# 2_byte_input.net
KiCad netlist of a schematic drawn in EAGLE
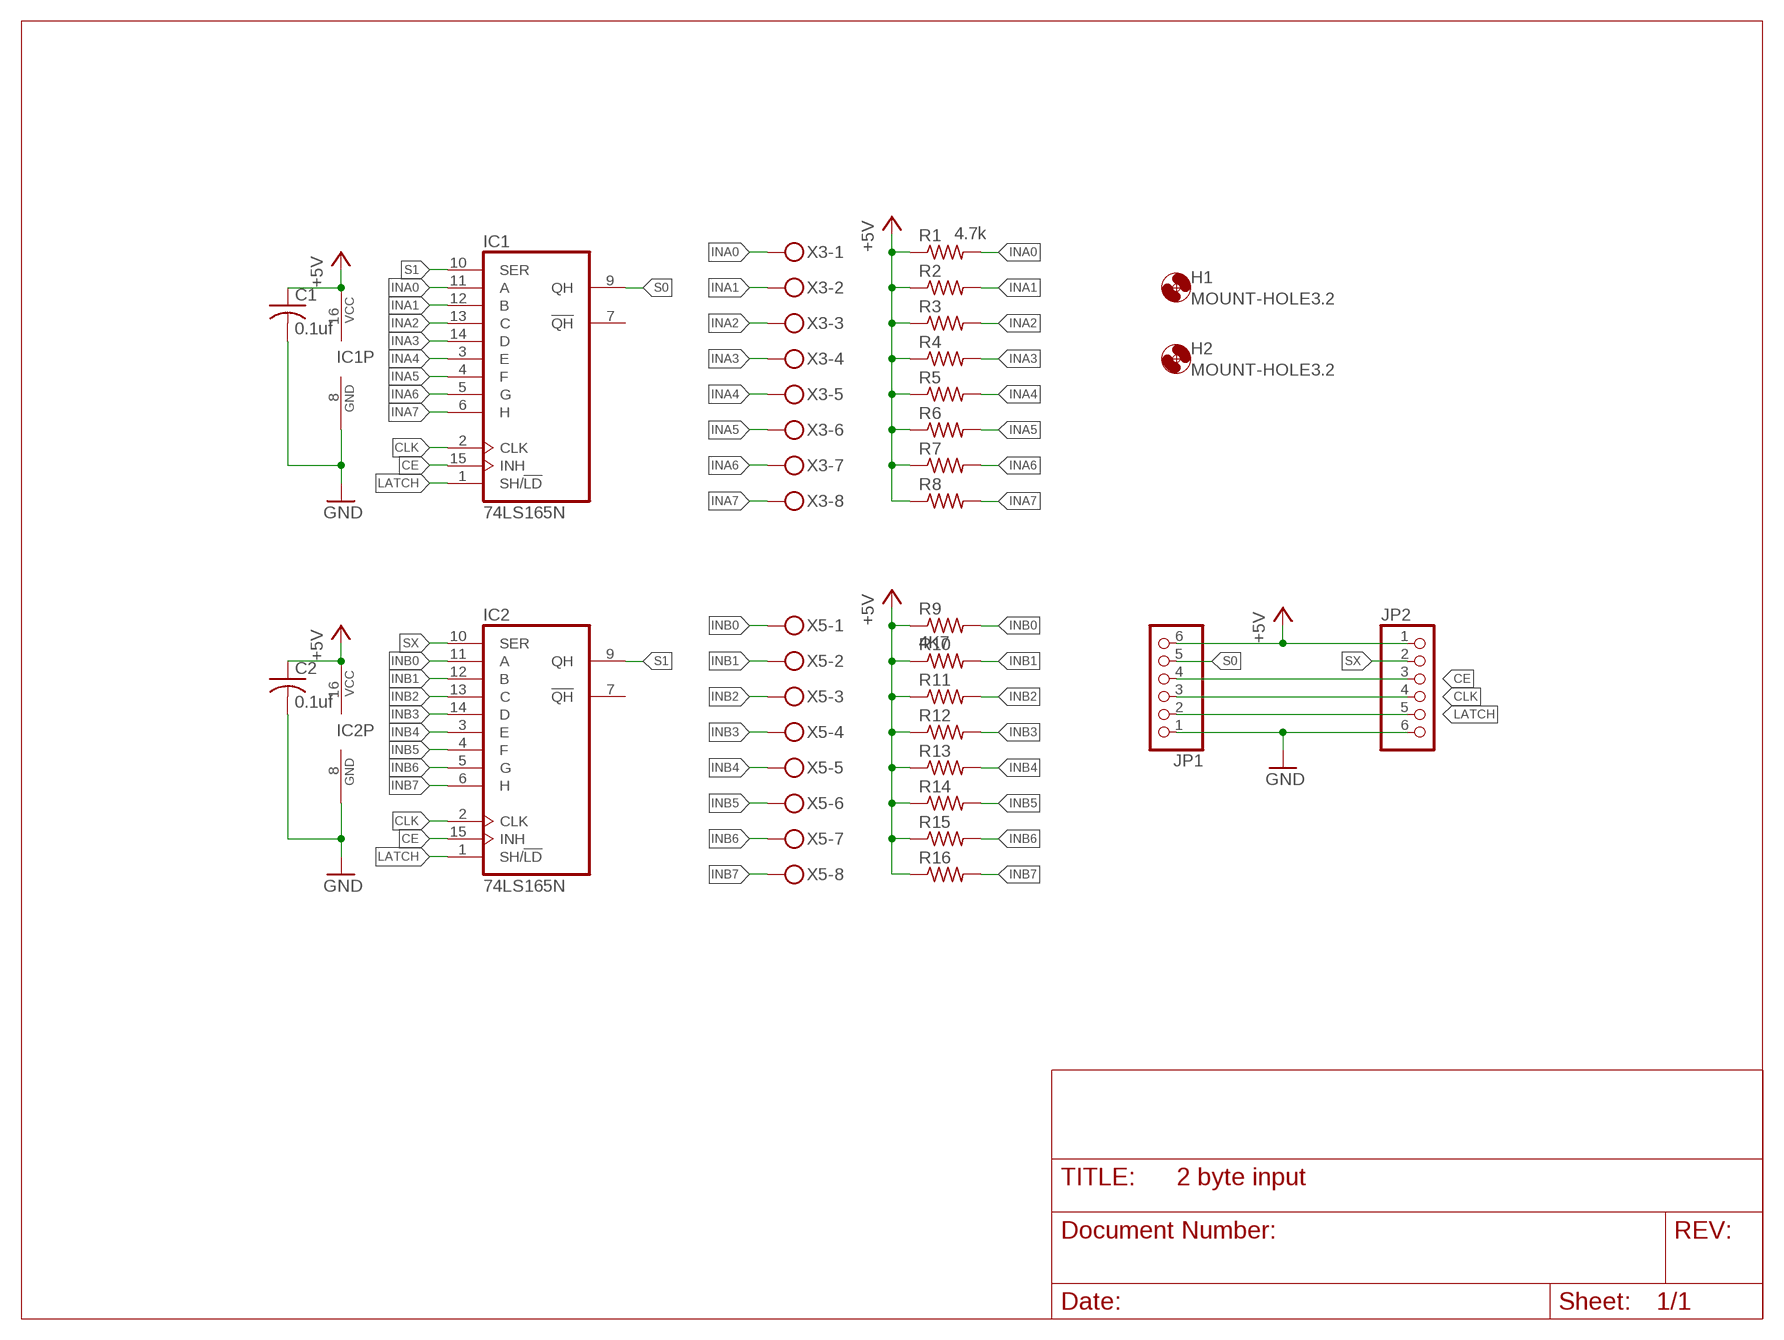
[diagram p0: schematic, sheet 1]

(export (version "E")
  (design (tool "Eeschema 10.0.6"))
  (components
    (comp (ref "C1")
      (value "0.1uf")
      (footprint "eagle-import:C025-025X050")
      (libsource (lib "eagle-import") (part "C-US025-025X050"))
    )
    (comp (ref "C2")
      (value "0.1uf")
      (footprint "eagle-import:C025-025X050")
      (libsource (lib "eagle-import") (part "C-US025-025X050"))
    )
    (comp (ref "H1")
      (value "MOUNT-HOLE3.2")
      (footprint "eagle-import:3,2")
      (libsource (lib "eagle-import") (part "MOUNT-HOLE3.2"))
    )
    (comp (ref "H2")
      (value "MOUNT-HOLE3.2")
      (footprint "eagle-import:3,2")
      (libsource (lib "eagle-import") (part "MOUNT-HOLE3.2"))
    )
    (comp (ref "IC1")
      (value "74LS165N")
      (footprint "eagle-import:DIL16")
      (libsource (lib "eagle-import") (part "74165NLS"))
    )
    (comp (ref "IC2")
      (value "74LS165N")
      (footprint "eagle-import:DIL16")
      (libsource (lib "eagle-import") (part "74165NLS"))
    )
    (comp (ref "JP1")
      (value "PINHD-1X6/90")
      (footprint "eagle-import:1X06_90")
      (libsource (lib "eagle-import") (part "PINHD-1X6/90"))
    )
    (comp (ref "JP2")
      (value "PINHD-1X6/90")
      (footprint "eagle-import:1X06_90")
      (libsource (lib "eagle-import") (part "PINHD-1X6/90"))
    )
    (comp (ref "R1")
      (value "4.7k")
      (footprint "eagle-import:0207_2V")
      (libsource (lib "eagle-import") (part "R-US_0207/2V"))
    )
    (comp (ref "R2")
      (value "R-US_0207/2V")
      (footprint "eagle-import:0207_2V")
      (libsource (lib "eagle-import") (part "R-US_0207/2V"))
    )
    (comp (ref "R3")
      (value "R-US_0207/2V")
      (footprint "eagle-import:0207_2V")
      (libsource (lib "eagle-import") (part "R-US_0207/2V"))
    )
    (comp (ref "R4")
      (value "R-US_0207/2V")
      (footprint "eagle-import:0207_2V")
      (libsource (lib "eagle-import") (part "R-US_0207/2V"))
    )
    (comp (ref "R5")
      (value "R-US_0207/2V")
      (footprint "eagle-import:0207_2V")
      (libsource (lib "eagle-import") (part "R-US_0207/2V"))
    )
    (comp (ref "R6")
      (value "R-US_0207/2V")
      (footprint "eagle-import:0207_2V")
      (libsource (lib "eagle-import") (part "R-US_0207/2V"))
    )
    (comp (ref "R7")
      (value "R-US_0207/2V")
      (footprint "eagle-import:0207_2V")
      (libsource (lib "eagle-import") (part "R-US_0207/2V"))
    )
    (comp (ref "R8")
      (value "R-US_0207/2V")
      (footprint "eagle-import:0207_2V")
      (libsource (lib "eagle-import") (part "R-US_0207/2V"))
    )
    (comp (ref "R9")
      (value "4K7")
      (footprint "eagle-import:0207_2V")
      (libsource (lib "eagle-import") (part "R-US_0207/2V"))
    )
    (comp (ref "R10")
      (value "R-US_0207/2V")
      (footprint "eagle-import:0207_2V")
      (libsource (lib "eagle-import") (part "R-US_0207/2V"))
    )
    (comp (ref "R11")
      (value "R-US_0207/2V")
      (footprint "eagle-import:0207_2V")
      (libsource (lib "eagle-import") (part "R-US_0207/2V"))
    )
    (comp (ref "R12")
      (value "R-US_0207/2V")
      (footprint "eagle-import:0207_2V")
      (libsource (lib "eagle-import") (part "R-US_0207/2V"))
    )
    (comp (ref "R13")
      (value "R-US_0207/2V")
      (footprint "eagle-import:0207_2V")
      (libsource (lib "eagle-import") (part "R-US_0207/2V"))
    )
    (comp (ref "R14")
      (value "R-US_0207/2V")
      (footprint "eagle-import:0207_2V")
      (libsource (lib "eagle-import") (part "R-US_0207/2V"))
    )
    (comp (ref "R15")
      (value "R-US_0207/2V")
      (footprint "eagle-import:0207_2V")
      (libsource (lib "eagle-import") (part "R-US_0207/2V"))
    )
    (comp (ref "R16")
      (value "R-US_0207/2V")
      (footprint "eagle-import:0207_2V")
      (libsource (lib "eagle-import") (part "R-US_0207/2V"))
    )
    (comp (ref "X3")
      (value "MKDSN1,5/8-5,08")
      (footprint "eagle-import:MKDSN1,5_8-5,08")
      (libsource (lib "eagle-import") (part "MKDSN1,5/8-5,08"))
    )
    (comp (ref "X5")
      (value "MKDSN1,5/8-5,08")
      (footprint "eagle-import:MKDSN1,5_8-5,08")
      (libsource (lib "eagle-import") (part "MKDSN1,5/8-5,08"))
    )
  )
  (nets
    (net (code "1") (name "+5V") (class "Default")
      (node (ref "C1") (pin "1") (pinfunction "1_1") (pintype "passive"))
      (node (ref "C2") (pin "1") (pinfunction "1_1") (pintype "passive"))
      (node (ref "IC1") (pin "16") (pinfunction "VCC_16") (pintype "power_in"))
      (node (ref "IC2") (pin "16") (pinfunction "VCC_16") (pintype "power_in"))
      (node (ref "JP1") (pin "6") (pinfunction "6_6") (pintype "passive"))
      (node (ref "JP2") (pin "1") (pinfunction "1_1") (pintype "passive"))
      (node (ref "R1") (pin "1") (pinfunction "1_1") (pintype "passive"))
      (node (ref "R10") (pin "1") (pinfunction "1_1") (pintype "passive"))
      (node (ref "R11") (pin "1") (pinfunction "1_1") (pintype "passive"))
      (node (ref "R12") (pin "1") (pinfunction "1_1") (pintype "passive"))
      (node (ref "R13") (pin "1") (pinfunction "1_1") (pintype "passive"))
      (node (ref "R14") (pin "1") (pinfunction "1_1") (pintype "passive"))
      (node (ref "R15") (pin "1") (pinfunction "1_1") (pintype "passive"))
      (node (ref "R16") (pin "1") (pinfunction "1_1") (pintype "passive"))
      (node (ref "R2") (pin "1") (pinfunction "1_1") (pintype "passive"))
      (node (ref "R3") (pin "1") (pinfunction "1_1") (pintype "passive"))
      (node (ref "R4") (pin "1") (pinfunction "1_1") (pintype "passive"))
      (node (ref "R5") (pin "1") (pinfunction "1_1") (pintype "passive"))
      (node (ref "R6") (pin "1") (pinfunction "1_1") (pintype "passive"))
      (node (ref "R7") (pin "1") (pinfunction "1_1") (pintype "passive"))
      (node (ref "R8") (pin "1") (pinfunction "1_1") (pintype "passive"))
      (node (ref "R9") (pin "1") (pinfunction "1_1") (pintype "passive"))
    )
    (net (code "2") (name "CE") (class "Default")
      (node (ref "IC1") (pin "15") (pinfunction "INH_15") (pintype "input"))
      (node (ref "IC2") (pin "15") (pinfunction "INH_15") (pintype "input"))
      (node (ref "JP1") (pin "4") (pinfunction "4_4") (pintype "passive"))
      (node (ref "JP2") (pin "3") (pinfunction "3_3") (pintype "passive"))
    )
    (net (code "3") (name "CLK") (class "Default")
      (node (ref "IC1") (pin "2") (pinfunction "CLK_2") (pintype "input"))
      (node (ref "IC2") (pin "2") (pinfunction "CLK_2") (pintype "input"))
      (node (ref "JP1") (pin "3") (pinfunction "3_3") (pintype "passive"))
      (node (ref "JP2") (pin "4") (pinfunction "4_4") (pintype "passive"))
    )
    (net (code "4") (name "GND") (class "Default")
      (node (ref "C1") (pin "2") (pinfunction "2_2") (pintype "passive"))
      (node (ref "C2") (pin "2") (pinfunction "2_2") (pintype "passive"))
      (node (ref "IC1") (pin "8") (pinfunction "GND_8") (pintype "power_in"))
      (node (ref "IC2") (pin "8") (pinfunction "GND_8") (pintype "power_in"))
      (node (ref "JP1") (pin "1") (pinfunction "1_1") (pintype "passive"))
      (node (ref "JP2") (pin "6") (pinfunction "6_6") (pintype "passive"))
    )
    (net (code "5") (name "INA0") (class "Default")
      (node (ref "IC1") (pin "11") (pinfunction "A_11") (pintype "input"))
      (node (ref "R1") (pin "2") (pinfunction "2_2") (pintype "passive"))
      (node (ref "X3") (pin "1") (pinfunction "KL_1") (pintype "passive"))
    )
    (net (code "6") (name "INA1") (class "Default")
      (node (ref "IC1") (pin "12") (pinfunction "B_12") (pintype "input"))
      (node (ref "R2") (pin "2") (pinfunction "2_2") (pintype "passive"))
      (node (ref "X3") (pin "2") (pinfunction "KL_2") (pintype "passive"))
    )
    (net (code "7") (name "INA2") (class "Default")
      (node (ref "IC1") (pin "13") (pinfunction "C_13") (pintype "input"))
      (node (ref "R3") (pin "2") (pinfunction "2_2") (pintype "passive"))
      (node (ref "X3") (pin "3") (pinfunction "KL_3") (pintype "passive"))
    )
    (net (code "8") (name "INA3") (class "Default")
      (node (ref "IC1") (pin "14") (pinfunction "D_14") (pintype "input"))
      (node (ref "R4") (pin "2") (pinfunction "2_2") (pintype "passive"))
      (node (ref "X3") (pin "4") (pinfunction "KL_4") (pintype "passive"))
    )
    (net (code "9") (name "INA4") (class "Default")
      (node (ref "IC1") (pin "3") (pinfunction "E_3") (pintype "input"))
      (node (ref "R5") (pin "2") (pinfunction "2_2") (pintype "passive"))
      (node (ref "X3") (pin "5") (pinfunction "KL_5") (pintype "passive"))
    )
    (net (code "10") (name "INA5") (class "Default")
      (node (ref "IC1") (pin "4") (pinfunction "F_4") (pintype "input"))
      (node (ref "R6") (pin "2") (pinfunction "2_2") (pintype "passive"))
      (node (ref "X3") (pin "6") (pinfunction "KL_6") (pintype "passive"))
    )
    (net (code "11") (name "INA6") (class "Default")
      (node (ref "IC1") (pin "5") (pinfunction "G_5") (pintype "input"))
      (node (ref "R7") (pin "2") (pinfunction "2_2") (pintype "passive"))
      (node (ref "X3") (pin "7") (pinfunction "KL_7") (pintype "passive"))
    )
    (net (code "12") (name "INA7") (class "Default")
      (node (ref "IC1") (pin "6") (pinfunction "H_6") (pintype "input"))
      (node (ref "R8") (pin "2") (pinfunction "2_2") (pintype "passive"))
      (node (ref "X3") (pin "8") (pinfunction "KL_8") (pintype "passive"))
    )
    (net (code "13") (name "INB0") (class "Default")
      (node (ref "IC2") (pin "11") (pinfunction "A_11") (pintype "input"))
      (node (ref "R9") (pin "2") (pinfunction "2_2") (pintype "passive"))
      (node (ref "X5") (pin "1") (pinfunction "KL_1") (pintype "passive"))
    )
    (net (code "14") (name "INB1") (class "Default")
      (node (ref "IC2") (pin "12") (pinfunction "B_12") (pintype "input"))
      (node (ref "R10") (pin "2") (pinfunction "2_2") (pintype "passive"))
      (node (ref "X5") (pin "2") (pinfunction "KL_2") (pintype "passive"))
    )
    (net (code "15") (name "INB2") (class "Default")
      (node (ref "IC2") (pin "13") (pinfunction "C_13") (pintype "input"))
      (node (ref "R11") (pin "2") (pinfunction "2_2") (pintype "passive"))
      (node (ref "X5") (pin "3") (pinfunction "KL_3") (pintype "passive"))
    )
    (net (code "16") (name "INB3") (class "Default")
      (node (ref "IC2") (pin "14") (pinfunction "D_14") (pintype "input"))
      (node (ref "R12") (pin "2") (pinfunction "2_2") (pintype "passive"))
      (node (ref "X5") (pin "4") (pinfunction "KL_4") (pintype "passive"))
    )
    (net (code "17") (name "INB4") (class "Default")
      (node (ref "IC2") (pin "3") (pinfunction "E_3") (pintype "input"))
      (node (ref "R13") (pin "2") (pinfunction "2_2") (pintype "passive"))
      (node (ref "X5") (pin "5") (pinfunction "KL_5") (pintype "passive"))
    )
    (net (code "18") (name "INB5") (class "Default")
      (node (ref "IC2") (pin "4") (pinfunction "F_4") (pintype "input"))
      (node (ref "R14") (pin "2") (pinfunction "2_2") (pintype "passive"))
      (node (ref "X5") (pin "6") (pinfunction "KL_6") (pintype "passive"))
    )
    (net (code "19") (name "INB6") (class "Default")
      (node (ref "IC2") (pin "5") (pinfunction "G_5") (pintype "input"))
      (node (ref "R15") (pin "2") (pinfunction "2_2") (pintype "passive"))
      (node (ref "X5") (pin "7") (pinfunction "KL_7") (pintype "passive"))
    )
    (net (code "20") (name "INB7") (class "Default")
      (node (ref "IC2") (pin "6") (pinfunction "H_6") (pintype "input"))
      (node (ref "R16") (pin "2") (pinfunction "2_2") (pintype "passive"))
      (node (ref "X5") (pin "8") (pinfunction "KL_8") (pintype "passive"))
    )
    (net (code "21") (name "LATCH") (class "Default")
      (node (ref "IC1") (pin "1") (pinfunction "SH/~{LD}_1") (pintype "input"))
      (node (ref "IC2") (pin "1") (pinfunction "SH/~{LD}_1") (pintype "input"))
      (node (ref "JP1") (pin "2") (pinfunction "2_2") (pintype "passive"))
      (node (ref "JP2") (pin "5") (pinfunction "5_5") (pintype "passive"))
    )
    (net (code "22") (name "S0") (class "Default")
      (node (ref "IC1") (pin "9") (pinfunction "QH_9") (pintype "output"))
      (node (ref "JP1") (pin "5") (pinfunction "5_5") (pintype "passive"))
    )
    (net (code "23") (name "S1") (class "Default")
      (node (ref "IC1") (pin "10") (pinfunction "SER_10") (pintype "input"))
      (node (ref "IC2") (pin "9") (pinfunction "QH_9") (pintype "output"))
    )
    (net (code "24") (name "SX") (class "Default")
      (node (ref "IC2") (pin "10") (pinfunction "SER_10") (pintype "input"))
      (node (ref "JP2") (pin "2") (pinfunction "2_2") (pintype "passive"))
    )
    (net (code "25") (name "unconnected-(IC1A-~{QH}-Pad7)") (class "Default")
      (node (ref "IC1") (pin "7") (pinfunction "~{QH}_7") (pintype "output"))
    )
    (net (code "26") (name "unconnected-(IC2A-~{QH}-Pad7)") (class "Default")
      (node (ref "IC2") (pin "7") (pinfunction "~{QH}_7") (pintype "output"))
    )
  )
)
